# M_2_NVME.net
KiCad netlist of a schematic drawn in Altium Designer
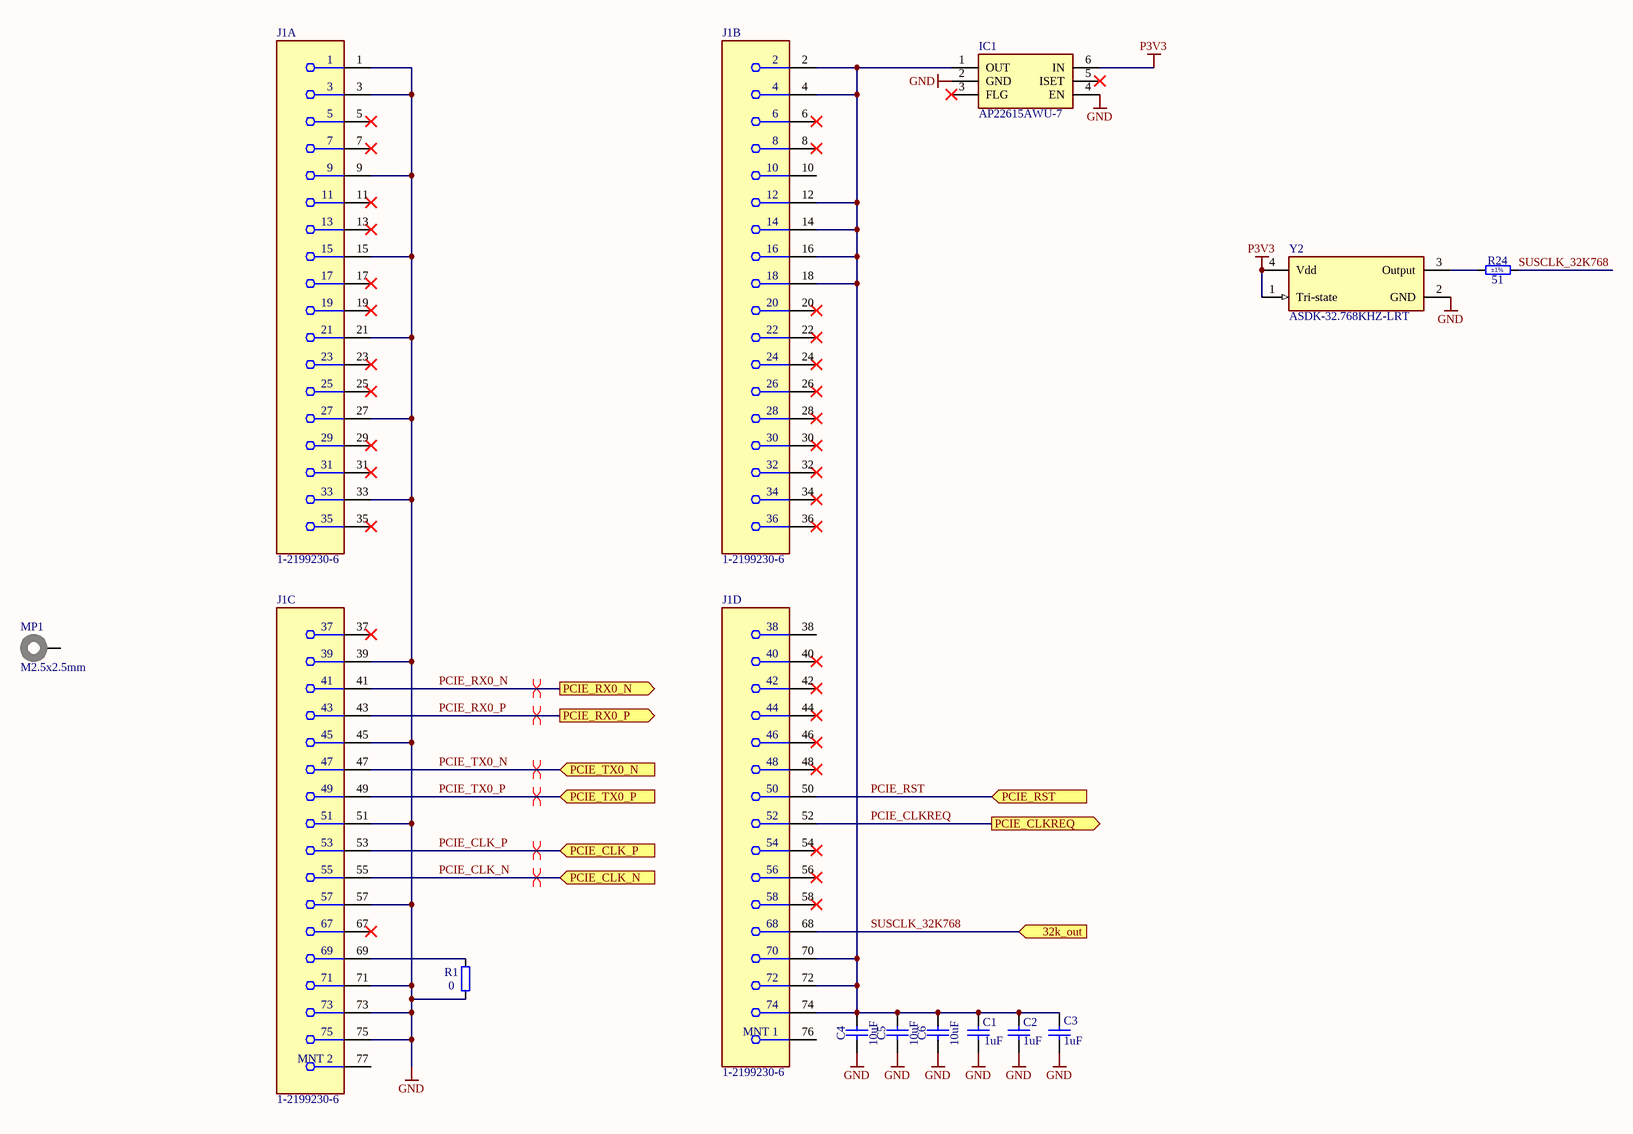
[diagram p0: M.2_NVME.SchDoc]

(export (version "E")
  (design (tool "Eeschema 10.0.6"))
  (components
    (comp (ref "C1")
      (value "1uF")
      (footprint "CAPC1005X55N")
      (description "Non-polarised capacitor")
      (fields
        (field (name "PART NUMBER") "CC0402_1UF_16V_10%_X5R")
        (field (name "VOLTAGE") "16V")
        (field (name "AUTHOR") "CERN DEM JLC")
      )
      (libsource (lib "Capacitors") (part "Capacitor - non polarized"))
    )
    (comp (ref "C2")
      (value "1uF")
      (footprint "CAPC1005X55N")
      (description "Non-polarised capacitor")
      (fields
        (field (name "PART NUMBER") "CC0402_1UF_16V_10%_X5R")
        (field (name "VOLTAGE") "16V")
        (field (name "AUTHOR") "CERN DEM JLC")
      )
      (libsource (lib "Capacitors") (part "Capacitor - non polarized"))
    )
    (comp (ref "C3")
      (value "1uF")
      (footprint "CAPC1005X55N")
      (description "Non-polarised capacitor")
      (fields
        (field (name "PART NUMBER") "CC0402_1UF_16V_10%_X5R")
        (field (name "VOLTAGE") "16V")
        (field (name "AUTHOR") "CERN DEM JLC")
      )
      (libsource (lib "Capacitors") (part "Capacitor - non polarized"))
    )
    (comp (ref "C4")
      (value "10uF")
      (footprint "CAPC2012X95N")
      (description "Non-polarised capacitor")
      (fields
        (field (name "PART NUMBER") "CC0805_10UF_25V_10%_X5R")
        (field (name "VOLTAGE") "25V")
        (field (name "AUTHOR") "CERN DEM JLC")
      )
      (libsource (lib "Capacitors") (part "Capacitor - non polarized"))
    )
    (comp (ref "C5")
      (value "10uF")
      (footprint "CAPC2012X95N")
      (description "Non-polarised capacitor")
      (fields
        (field (name "PART NUMBER") "CC0805_10UF_25V_10%_X5R")
        (field (name "VOLTAGE") "25V")
        (field (name "AUTHOR") "CERN DEM JLC")
      )
      (libsource (lib "Capacitors") (part "Capacitor - non polarized"))
    )
    (comp (ref "C6")
      (value "10uF")
      (footprint "CAPC2012X95N")
      (description "Non-polarised capacitor")
      (fields
        (field (name "PART NUMBER") "CC0805_10UF_25V_10%_X5R")
        (field (name "VOLTAGE") "25V")
        (field (name "AUTHOR") "CERN DEM JLC")
      )
      (libsource (lib "Capacitors") (part "Capacitor - non polarized"))
    )
    (comp (ref "IC1")
      (value "AP22615AWU-7")
      (footprint "SamacSys:SOT95P280X100-6N")
      (description "Integrated Circuit")
      (libsource (lib "*") (part "AP22615AWU-7"))
    )
    (comp (ref "J1")
      (value "1-2199230-6")
      (footprint "FP-1-2199230-6-MFG")
      (description "CONN EDGE DUAL FMALE 67POS 0.020")
      (fields
        (field (name "MANUFACTURER") "TE")
        (field (name "OCTOPART") "https://octopart.com/1-2199230-6-te+connectivity-34969376")
      )
      (libsource (lib "Altium Content Vault") (part "bdc5cd39fb5e3adfc3cf7d042564072"))
    )
    (comp (ref "MP1")
      (value "M2.5x2.5mm")
      (footprint "9774025151")
      (description "WA-SMSI SMT Steel Spacer, internal Thread, OD 5.1mm, M2.5x2.5mm")
      (fields
        (field (name "MANUFACTURER PART NUMBER") "9774025151")
        (field (name "MANUFACTURER") "Wurth Elektronik")
      )
      (libsource (lib "Altium_WA-SMSI (rev21a)") (part "9774025151"))
    )
    (comp (ref "R1")
      (value "0")
      (footprint "RESC1005X40N")
      (description "Resistor")
      (fields
        (field (name "PART NUMBER") "R0402_0R_JUMPER")
        (field (name "MANUFACTURER") "GENERIC")
        (field (name "AUTHOR") "CERN DEM JLC")
      )
      (libsource (lib "Resistors") (part "Resistor"))
    )
    (comp (ref "R24")
      (value "51")
      (footprint "RESC1005X40N")
      (description "Resistor - 1%")
      (fields
        (field (name "TOLERANCE") "±1%")
        (field (name "PART NUMBER") "R0402_51R_1%_0.0625W_100PPM")
        (field (name "POWER") "0.0625W")
        (field (name "AUTHOR") "CERN DEM JLC")
      )
      (libsource (lib "Resistors") (part "Resistor - 1%"))
    )
    (comp (ref "Y2")
      (value "ASDK-32.768KHZ-LRT")
      (footprint "FP-ASDK-MFG")
      (description "XTAL OSC XO 32.7680KHZ CMOS SMD")
      (libsource (lib "Altium Content Vault") (part "a7425352bb6ebc83bfd0f12a23808e7"))
    )
  )
  (nets
    (net (code "1") (name "/PCIE_CLKREQ") (class "Default")
      (node (ref "J1") (pin "52") (pinfunction "52_52") (pintype "passive"))
    )
    (net (code "2") (name "/PCIE_CLK_N") (class "Default")
      (node (ref "J1") (pin "55") (pinfunction "55_55") (pintype "passive"))
    )
    (net (code "3") (name "/PCIE_CLK_P") (class "Default")
      (node (ref "J1") (pin "53") (pinfunction "53_53") (pintype "passive"))
    )
    (net (code "4") (name "/PCIE_RST") (class "Default")
      (node (ref "J1") (pin "50") (pinfunction "50_50") (pintype "passive"))
    )
    (net (code "5") (name "/PCIE_RX0_N") (class "Default")
      (node (ref "J1") (pin "41") (pinfunction "41_41") (pintype "passive"))
    )
    (net (code "6") (name "/PCIE_RX0_P") (class "Default")
      (node (ref "J1") (pin "43") (pinfunction "43_43") (pintype "passive"))
    )
    (net (code "7") (name "/PCIE_TX0_N") (class "Default")
      (node (ref "J1") (pin "47") (pinfunction "47_47") (pintype "passive"))
    )
    (net (code "8") (name "/PCIE_TX0_P") (class "Default")
      (node (ref "J1") (pin "49") (pinfunction "49_49") (pintype "passive"))
    )
    (net (code "9") (name "/SUSCLK_32K768") (class "Default")
      (node (ref "J1") (pin "68") (pinfunction "68_68") (pintype "passive"))
      (node (ref "R24") (pin "2") (pinfunction "2_2") (pintype "passive"))
    )
    (net (code "10") (name "GND") (class "Default")
      (node (ref "C1") (pin "1") (pinfunction "1_1") (pintype "passive"))
      (node (ref "C2") (pin "1") (pinfunction "1_1") (pintype "passive"))
      (node (ref "C3") (pin "1") (pinfunction "1_1") (pintype "passive"))
      (node (ref "C4") (pin "1") (pinfunction "1_1") (pintype "passive"))
      (node (ref "C5") (pin "1") (pinfunction "1_1") (pintype "passive"))
      (node (ref "C6") (pin "1") (pinfunction "1_1") (pintype "passive"))
      (node (ref "IC1") (pin "2") (pinfunction "GND_2") (pintype "passive"))
      (node (ref "IC1") (pin "4") (pinfunction "EN_4") (pintype "passive"))
      (node (ref "J1") (pin "1") (pinfunction "1_1") (pintype "passive"))
      (node (ref "J1") (pin "15") (pinfunction "15_15") (pintype "passive"))
      (node (ref "J1") (pin "21") (pinfunction "21_21") (pintype "passive"))
      (node (ref "J1") (pin "27") (pinfunction "27_27") (pintype "passive"))
      (node (ref "J1") (pin "3") (pinfunction "3_3") (pintype "passive"))
      (node (ref "J1") (pin "33") (pinfunction "33_33") (pintype "passive"))
      (node (ref "J1") (pin "39") (pinfunction "39_39") (pintype "passive"))
      (node (ref "J1") (pin "45") (pinfunction "45_45") (pintype "passive"))
      (node (ref "J1") (pin "51") (pinfunction "51_51") (pintype "passive"))
      (node (ref "J1") (pin "57") (pinfunction "57_57") (pintype "passive"))
      (node (ref "J1") (pin "71") (pinfunction "71_71") (pintype "passive"))
      (node (ref "J1") (pin "73") (pinfunction "73_73") (pintype "passive"))
      (node (ref "J1") (pin "75") (pinfunction "75_75") (pintype "passive"))
      (node (ref "J1") (pin "9") (pinfunction "9_9") (pintype "passive"))
      (node (ref "R1") (pin "1") (pinfunction "1_1") (pintype "passive"))
      (node (ref "Y2") (pin "2") (pinfunction "GND_2") (pintype "power_in"))
    )
    (net (code "11") (name "Net-(IC1-OUT)") (class "Default")
      (node (ref "C1") (pin "2") (pinfunction "2_2") (pintype "passive"))
      (node (ref "C2") (pin "2") (pinfunction "2_2") (pintype "passive"))
      (node (ref "C3") (pin "2") (pinfunction "2_2") (pintype "passive"))
      (node (ref "C4") (pin "2") (pinfunction "2_2") (pintype "passive"))
      (node (ref "C5") (pin "2") (pinfunction "2_2") (pintype "passive"))
      (node (ref "C6") (pin "2") (pinfunction "2_2") (pintype "passive"))
      (node (ref "IC1") (pin "1") (pinfunction "OUT_1") (pintype "passive"))
      (node (ref "J1") (pin "12") (pinfunction "12_12") (pintype "passive"))
      (node (ref "J1") (pin "14") (pinfunction "14_14") (pintype "passive"))
      (node (ref "J1") (pin "16") (pinfunction "16_16") (pintype "passive"))
      (node (ref "J1") (pin "18") (pinfunction "18_18") (pintype "passive"))
      (node (ref "J1") (pin "2") (pinfunction "2_2") (pintype "passive"))
      (node (ref "J1") (pin "4") (pinfunction "4_4") (pintype "passive"))
      (node (ref "J1") (pin "70") (pinfunction "70_70") (pintype "passive"))
      (node (ref "J1") (pin "72") (pinfunction "72_72") (pintype "passive"))
      (node (ref "J1") (pin "74") (pinfunction "74_74") (pintype "passive"))
    )
    (net (code "12") (name "Net-(J1-Pad69)") (class "Default")
      (node (ref "J1") (pin "69") (pinfunction "69_69") (pintype "passive"))
      (node (ref "R1") (pin "2") (pinfunction "2_2") (pintype "passive"))
    )
    (net (code "13") (name "Net-(Y2-Output)") (class "Default")
      (node (ref "R24") (pin "1") (pinfunction "1_1") (pintype "passive"))
      (node (ref "Y2") (pin "3") (pinfunction "Output_3") (pintype "tri_state"))
    )
    (net (code "14") (name "P3V3") (class "Default")
      (node (ref "IC1") (pin "6") (pinfunction "IN_6") (pintype "passive"))
      (node (ref "Y2") (pin "1") (pinfunction "Tri-state_1") (pintype "input"))
      (node (ref "Y2") (pin "4") (pinfunction "Vdd_4") (pintype "power_in"))
    )
    (net (code "15") (name "unconnected-(IC1-FLG-Pad3)") (class "Default")
      (node (ref "IC1") (pin "3") (pinfunction "FLG_3") (pintype "passive+no_connect"))
    )
    (net (code "16") (name "unconnected-(IC1-ISET-Pad5)") (class "Default")
      (node (ref "IC1") (pin "5") (pinfunction "ISET_5") (pintype "passive+no_connect"))
    )
    (net (code "17") (name "unconnected-(J1-Pad5)") (class "Default")
      (node (ref "J1") (pin "5") (pinfunction "5_5") (pintype "passive+no_connect"))
    )
    (net (code "18") (name "unconnected-(J1-Pad6)") (class "Default")
      (node (ref "J1") (pin "6") (pinfunction "6_6") (pintype "passive+no_connect"))
    )
    (net (code "19") (name "unconnected-(J1-Pad7)") (class "Default")
      (node (ref "J1") (pin "7") (pinfunction "7_7") (pintype "passive+no_connect"))
    )
    (net (code "20") (name "unconnected-(J1-Pad8)") (class "Default")
      (node (ref "J1") (pin "8") (pinfunction "8_8") (pintype "passive+no_connect"))
    )
    (net (code "21") (name "unconnected-(J1-Pad10)") (class "Default")
      (node (ref "J1") (pin "10") (pinfunction "10_10") (pintype "passive"))
    )
    (net (code "22") (name "unconnected-(J1-Pad11)") (class "Default")
      (node (ref "J1") (pin "11") (pinfunction "11_11") (pintype "passive+no_connect"))
    )
    (net (code "23") (name "unconnected-(J1-Pad13)") (class "Default")
      (node (ref "J1") (pin "13") (pinfunction "13_13") (pintype "passive+no_connect"))
    )
    (net (code "24") (name "unconnected-(J1-Pad17)") (class "Default")
      (node (ref "J1") (pin "17") (pinfunction "17_17") (pintype "passive+no_connect"))
    )
    (net (code "25") (name "unconnected-(J1-Pad19)") (class "Default")
      (node (ref "J1") (pin "19") (pinfunction "19_19") (pintype "passive+no_connect"))
    )
    (net (code "26") (name "unconnected-(J1-Pad20)") (class "Default")
      (node (ref "J1") (pin "20") (pinfunction "20_20") (pintype "passive+no_connect"))
    )
    (net (code "27") (name "unconnected-(J1-Pad22)") (class "Default")
      (node (ref "J1") (pin "22") (pinfunction "22_22") (pintype "passive+no_connect"))
    )
    (net (code "28") (name "unconnected-(J1-Pad23)") (class "Default")
      (node (ref "J1") (pin "23") (pinfunction "23_23") (pintype "passive+no_connect"))
    )
    (net (code "29") (name "unconnected-(J1-Pad24)") (class "Default")
      (node (ref "J1") (pin "24") (pinfunction "24_24") (pintype "passive+no_connect"))
    )
    (net (code "30") (name "unconnected-(J1-Pad25)") (class "Default")
      (node (ref "J1") (pin "25") (pinfunction "25_25") (pintype "passive+no_connect"))
    )
    (net (code "31") (name "unconnected-(J1-Pad26)") (class "Default")
      (node (ref "J1") (pin "26") (pinfunction "26_26") (pintype "passive+no_connect"))
    )
    (net (code "32") (name "unconnected-(J1-Pad28)") (class "Default")
      (node (ref "J1") (pin "28") (pinfunction "28_28") (pintype "passive+no_connect"))
    )
    (net (code "33") (name "unconnected-(J1-Pad29)") (class "Default")
      (node (ref "J1") (pin "29") (pinfunction "29_29") (pintype "passive+no_connect"))
    )
    (net (code "34") (name "unconnected-(J1-Pad30)") (class "Default")
      (node (ref "J1") (pin "30") (pinfunction "30_30") (pintype "passive+no_connect"))
    )
    (net (code "35") (name "unconnected-(J1-Pad31)") (class "Default")
      (node (ref "J1") (pin "31") (pinfunction "31_31") (pintype "passive+no_connect"))
    )
    (net (code "36") (name "unconnected-(J1-Pad32)") (class "Default")
      (node (ref "J1") (pin "32") (pinfunction "32_32") (pintype "passive+no_connect"))
    )
    (net (code "37") (name "unconnected-(J1-Pad34)") (class "Default")
      (node (ref "J1") (pin "34") (pinfunction "34_34") (pintype "passive+no_connect"))
    )
    (net (code "38") (name "unconnected-(J1-Pad35)") (class "Default")
      (node (ref "J1") (pin "35") (pinfunction "35_35") (pintype "passive+no_connect"))
    )
    (net (code "39") (name "unconnected-(J1-Pad36)") (class "Default")
      (node (ref "J1") (pin "36") (pinfunction "36_36") (pintype "passive+no_connect"))
    )
    (net (code "40") (name "unconnected-(J1-Pad37)") (class "Default")
      (node (ref "J1") (pin "37") (pinfunction "37_37") (pintype "passive+no_connect"))
    )
    (net (code "41") (name "unconnected-(J1-Pad38)") (class "Default")
      (node (ref "J1") (pin "38") (pinfunction "38_38") (pintype "passive"))
    )
    (net (code "42") (name "unconnected-(J1-Pad40)") (class "Default")
      (node (ref "J1") (pin "40") (pinfunction "40_40") (pintype "passive+no_connect"))
    )
    (net (code "43") (name "unconnected-(J1-Pad42)") (class "Default")
      (node (ref "J1") (pin "42") (pinfunction "42_42") (pintype "passive+no_connect"))
    )
    (net (code "44") (name "unconnected-(J1-Pad44)") (class "Default")
      (node (ref "J1") (pin "44") (pinfunction "44_44") (pintype "passive+no_connect"))
    )
    (net (code "45") (name "unconnected-(J1-Pad46)") (class "Default")
      (node (ref "J1") (pin "46") (pinfunction "46_46") (pintype "passive+no_connect"))
    )
    (net (code "46") (name "unconnected-(J1-Pad48)") (class "Default")
      (node (ref "J1") (pin "48") (pinfunction "48_48") (pintype "passive+no_connect"))
    )
    (net (code "47") (name "unconnected-(J1-Pad54)") (class "Default")
      (node (ref "J1") (pin "54") (pinfunction "54_54") (pintype "passive+no_connect"))
    )
    (net (code "48") (name "unconnected-(J1-Pad56)") (class "Default")
      (node (ref "J1") (pin "56") (pinfunction "56_56") (pintype "passive+no_connect"))
    )
    (net (code "49") (name "unconnected-(J1-Pad58)") (class "Default")
      (node (ref "J1") (pin "58") (pinfunction "58_58") (pintype "passive+no_connect"))
    )
    (net (code "50") (name "unconnected-(J1-Pad67)") (class "Default")
      (node (ref "J1") (pin "67") (pinfunction "67_67") (pintype "passive+no_connect"))
    )
    (net (code "51") (name "unconnected-(J1C-MNT_2-Pad77)") (class "Default")
      (node (ref "J1") (pin "77") (pinfunction "MNT_2_77") (pintype "passive"))
    )
    (net (code "52") (name "unconnected-(J1D-MNT_1-Pad76)") (class "Default")
      (node (ref "J1") (pin "76") (pinfunction "MNT_1_76") (pintype "passive"))
    )
    (net (code "53") (name "unconnected-(MP1-Pad1)") (class "Default")
      (node (ref "MP1") (pin "1") (pinfunction "1_1") (pintype "passive"))
    )
  )
)
